# Schematic.net
KiCad netlist of a schematic drawn in Altium Designer
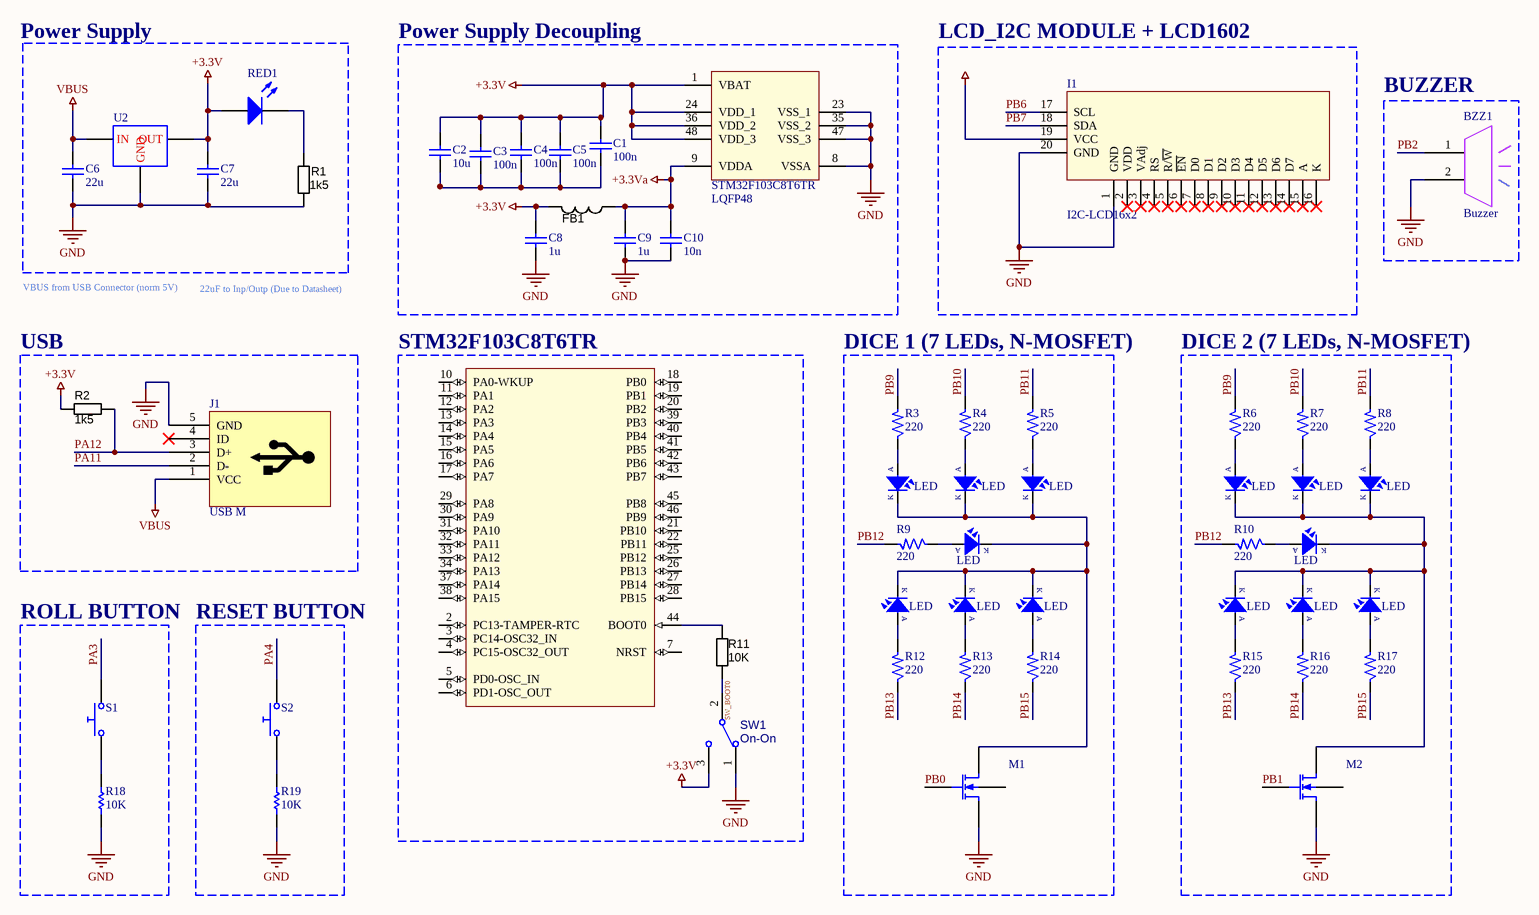
[diagram p0: Schematic.SchDoc]

(export (version "E")
  (design (tool "Eeschema 10.0.6"))
  (components
    (comp (ref "BZZ1")
      (value "Buzzer")
      (footprint "buzzer 5V")
      (libsource (lib "my Library") (part "Buzzer"))
    )
    (comp (ref "C1")
      (value "100n")
      (footprint "C 0402")
      (description "Capacitor")
      (libsource (lib "Simulation Generic Components") (part "Capacitor"))
    )
    (comp (ref "C2")
      (value "10u")
      (footprint "C 0402")
      (description "Capacitor")
      (libsource (lib "Simulation Generic Components") (part "Capacitor"))
    )
    (comp (ref "C3")
      (value "100n")
      (footprint "C 0402")
      (description "Capacitor")
      (libsource (lib "Simulation Generic Components") (part "Capacitor"))
    )
    (comp (ref "C4")
      (value "100n")
      (footprint "C 0402")
      (description "Capacitor")
      (libsource (lib "Simulation Generic Components") (part "Capacitor"))
    )
    (comp (ref "C5")
      (value "100n")
      (footprint "C 0402")
      (description "Capacitor")
      (libsource (lib "Simulation Generic Components") (part "Capacitor"))
    )
    (comp (ref "C6")
      (value "22u")
      (footprint "C 0805")
      (description "Capacitor")
      (libsource (lib "Simulation Generic Components") (part "Capacitor"))
    )
    (comp (ref "C7")
      (value "22u")
      (footprint "C 0805")
      (description "Capacitor")
      (libsource (lib "Simulation Generic Components") (part "Capacitor"))
    )
    (comp (ref "C8")
      (value "1u")
      (footprint "C 0402")
      (description "Capacitor")
      (libsource (lib "Simulation Generic Components") (part "Capacitor"))
    )
    (comp (ref "C9")
      (value "1u")
      (footprint "C 0402")
      (description "Capacitor")
      (libsource (lib "Simulation Generic Components") (part "Capacitor"))
    )
    (comp (ref "C10")
      (value "10n")
      (footprint "C 0402")
      (description "Capacitor")
      (libsource (lib "Simulation Generic Components") (part "Capacitor"))
    )
    (comp (ref "FB1")
      (value "2K2 @ 100 MHz")
      (footprint "FBC1608X95N")
      (description "Ferrite bead 120 Ohm at 100 MHz 200mA 0603 SMD")
      (libsource (lib "my Library") (part "FERRITE_2K2-100MHz_0603"))
    )
    (comp (ref "I1")
      (value "I2C-LCD16x2")
      (footprint "I2C-LCD16X2")
      (description "LCD dipslay 16 char, 2 line")
      (libsource (lib "my Library") (part "I2C-LCD16x2"))
    )
    (comp (ref "J1")
      (value "USB M")
      (footprint "USB-Micr-B-FCI-SMD")
      (libsource (lib "my Library") (part "USB M"))
    )
    (comp (ref "LED1")
      (value "LED")
      (footprint "LED-3")
      (description "LED Single colour Green and Red")
      (libsource (lib "my Library") (part "LED"))
    )
    (comp (ref "LED2")
      (value "LED")
      (footprint "LED-3")
      (description "LED Single colour Green and Red")
      (libsource (lib "my Library") (part "LED"))
    )
    (comp (ref "LED3")
      (value "LED")
      (footprint "LED-3")
      (description "LED Single colour Green and Red")
      (libsource (lib "my Library") (part "LED"))
    )
    (comp (ref "LED4")
      (value "LED")
      (footprint "LED-3")
      (description "LED Single colour Green and Red")
      (libsource (lib "my Library") (part "LED"))
    )
    (comp (ref "LED5")
      (value "LED")
      (footprint "LED-3")
      (description "LED Single colour Green and Red")
      (libsource (lib "my Library") (part "LED"))
    )
    (comp (ref "LED6")
      (value "LED")
      (footprint "LED-3")
      (description "LED Single colour Green and Red")
      (libsource (lib "my Library") (part "LED"))
    )
    (comp (ref "LED7")
      (value "LED")
      (footprint "LED-3")
      (description "LED Single colour Green and Red")
      (libsource (lib "my Library") (part "LED"))
    )
    (comp (ref "LED8")
      (value "LED")
      (footprint "LED-3")
      (description "LED Single colour Green and Red")
      (libsource (lib "my Library") (part "LED"))
    )
    (comp (ref "LED9")
      (value "LED")
      (footprint "LED-3")
      (description "LED Single colour Green and Red")
      (libsource (lib "my Library") (part "LED"))
    )
    (comp (ref "LED10")
      (value "LED")
      (footprint "LED-3")
      (description "LED Single colour Green and Red")
      (libsource (lib "my Library") (part "LED"))
    )
    (comp (ref "LED11")
      (value "LED")
      (footprint "LED-3")
      (description "LED Single colour Green and Red")
      (libsource (lib "my Library") (part "LED"))
    )
    (comp (ref "LED12")
      (value "LED")
      (footprint "LED-3")
      (description "LED Single colour Green and Red")
      (libsource (lib "my Library") (part "LED"))
    )
    (comp (ref "LED13")
      (value "LED")
      (footprint "LED-3")
      (description "LED Single colour Green and Red")
      (libsource (lib "my Library") (part "LED"))
    )
    (comp (ref "LED14")
      (value "LED")
      (footprint "LED-3")
      (description "LED Single colour Green and Red")
      (libsource (lib "my Library") (part "LED"))
    )
    (comp (ref "M1")
      (value "N-channel MOS1 MOSFET Shichman and Hodges Model")
      (libsource (lib "Simulation Generic Components") (part "MOSFET N-ch Lev1"))
    )
    (comp (ref "M2")
      (value "N-channel MOS1 MOSFET Shichman and Hodges Model")
      (libsource (lib "Simulation Generic Components") (part "MOSFET N-ch Lev1"))
    )
    (comp (ref "R1")
      (value "1k5")
      (footprint "RESC1005X40N")
      (description "Resistor SMD chip 1k Ohm 0.063W 5% 0402")
      (fields (field (name "TOLERANCE") "±5%") (field (name "Comment") "Thick Film"))
      (libsource (lib "my Library") (part "RES_0402"))
    )
    (comp (ref "R2")
      (value "1k5")
      (footprint "RESC1005X40N")
      (description "Resistor SMD chip 1k Ohm 0.063W 5% 0402")
      (fields (field (name "TOLERANCE") "±5%") (field (name "Comment") "Thick Film"))
      (libsource (lib "my Library") (part "RES_0402"))
    )
    (comp (ref "R3")
      (value "220")
      (footprint "R1/4W")
      (description "Res")
      (libsource (lib "my Library") (part "Res"))
    )
    (comp (ref "R4")
      (value "220")
      (footprint "R1/4W")
      (description "Res")
      (libsource (lib "my Library") (part "Res"))
    )
    (comp (ref "R5")
      (value "220")
      (footprint "R1/4W")
      (description "Res")
      (libsource (lib "my Library") (part "Res"))
    )
    (comp (ref "R6")
      (value "220")
      (footprint "R1/4W")
      (description "Res")
      (libsource (lib "my Library") (part "Res"))
    )
    (comp (ref "R7")
      (value "220")
      (footprint "R1/4W")
      (description "Res")
      (libsource (lib "my Library") (part "Res"))
    )
    (comp (ref "R8")
      (value "220")
      (footprint "R1/4W")
      (description "Res")
      (libsource (lib "my Library") (part "Res"))
    )
    (comp (ref "R9")
      (value "220")
      (footprint "R1/4W")
      (description "Res")
      (libsource (lib "my Library") (part "Res"))
    )
    (comp (ref "R10")
      (value "220")
      (footprint "R1/4W")
      (description "Res")
      (libsource (lib "my Library") (part "Res"))
    )
    (comp (ref "R11")
      (value "10K")
      (footprint "RESC1005X40N")
      (description "Resistor SMD chip 1k Ohm 0.063W 5% 0402")
      (fields (field (name "TOLERANCE") "±5%") (field (name "Comment") "Thick Film"))
      (libsource (lib "") (part "RES_0402_1"))
    )
    (comp (ref "R12")
      (value "220")
      (footprint "R1/4W")
      (description "Res")
      (libsource (lib "my Library") (part "Res"))
    )
    (comp (ref "R13")
      (value "220")
      (footprint "R1/4W")
      (description "Res")
      (libsource (lib "my Library") (part "Res"))
    )
    (comp (ref "R14")
      (value "220")
      (footprint "R1/4W")
      (description "Res")
      (libsource (lib "my Library") (part "Res"))
    )
    (comp (ref "R15")
      (value "220")
      (footprint "R1/4W")
      (description "Res")
      (libsource (lib "my Library") (part "Res"))
    )
    (comp (ref "R16")
      (value "220")
      (footprint "R1/4W")
      (description "Res")
      (libsource (lib "my Library") (part "Res"))
    )
    (comp (ref "R17")
      (value "220")
      (footprint "R1/4W")
      (description "Res")
      (libsource (lib "my Library") (part "Res"))
    )
    (comp (ref "R18")
      (value "10K")
      (description "Resistor")
      (libsource (lib "Simulation Generic Components") (part "Resistor"))
    )
    (comp (ref "R19")
      (value "10K")
      (description "Resistor")
      (libsource (lib "Simulation Generic Components") (part "Resistor"))
    )
    (comp (ref "RED1")
      (value "Light-Emitting Diode")
      (footprint "LED-RED-0805")
      (libsource (lib "Simulation Generic Components") (part "LED"))
    )
    (comp (ref "S1")
      (value "Push Button Normally Opened")
      (libsource (lib "Simulation Generic Components") (part "Push Button NO"))
    )
    (comp (ref "S2")
      (value "Push Button Normally Opened")
      (libsource (lib "Simulation Generic Components") (part "Push Button NO"))
    )
    (comp (ref "SW1")
      (value "ON-ON")
      (footprint "SW4_SMD")
      (description "Switch THD vertical toggle SPDT")
      (fields (field (name "SWITCH FUNCTION") "On-On"))
      (libsource (lib "my Library") (part "SW_THD_SPDT_On-On"))
    )
    (comp (ref "U1")
      (value "STM32F103C8T6TR")
      (footprint "STM-LQFP48_M")
      (fields (field (name "PACKAGE") "LQFP48"))
      (libsource (lib "mcu_stm32f1") (part "STM32F103C8T6TR"))
    )
    (comp (ref "U2")
      (value "Positive Fixed Voltage regulator")
      (footprint "AMS1117_3v3")
      (libsource (lib "Simulation Generic Components") (part "Linear Voltage Regulator (Fixed)"))
    )
  )
  (nets
    (net (code "1") (name "+3.3V") (class "Default")
      (node (ref "C1") (pin "1") (pinfunction "1_1") (pintype "passive"))
      (node (ref "C2") (pin "1") (pinfunction "1_1") (pintype "passive"))
      (node (ref "C3") (pin "1") (pinfunction "1_1") (pintype "passive"))
      (node (ref "C4") (pin "1") (pinfunction "1_1") (pintype "passive"))
      (node (ref "C5") (pin "1") (pinfunction "1_1") (pintype "passive"))
      (node (ref "C7") (pin "1") (pinfunction "1_1") (pintype "passive"))
      (node (ref "C8") (pin "1") (pinfunction "1_1") (pintype "passive"))
      (node (ref "FB1") (pin "2") (pinfunction "2_2") (pintype "passive"))
      (node (ref "R2") (pin "1") (pinfunction "1_1") (pintype "passive"))
      (node (ref "RED1") (pin "1") (pinfunction "A_1") (pintype "passive"))
      (node (ref "SW1") (pin "3") (pinfunction "3_3") (pintype "passive"))
      (node (ref "U1") (pin "1") (pinfunction "VBAT_1") (pintype "power_in"))
      (node (ref "U1") (pin "24") (pinfunction "VDD_1_24") (pintype "power_in"))
      (node (ref "U1") (pin "36") (pinfunction "VDD_2_36") (pintype "power_in"))
      (node (ref "U1") (pin "48") (pinfunction "VDD_3_48") (pintype "power_in"))
      (node (ref "U2") (pin "3") (pinfunction "OUT_3") (pintype "passive"))
    )
    (net (code "2") (name "+3.3Va") (class "Default")
      (node (ref "C10") (pin "1") (pinfunction "1_1") (pintype "passive"))
      (node (ref "C9") (pin "1") (pinfunction "1_1") (pintype "passive"))
      (node (ref "FB1") (pin "1") (pinfunction "1_1") (pintype "passive"))
      (node (ref "U1") (pin "9") (pinfunction "VDDA_9") (pintype "power_in"))
    )
    (net (code "3") (name "/PA3") (class "Default")
      (node (ref "S1") (pin "2") (pinfunction "2_2") (pintype "passive"))
    )
    (net (code "4") (name "/PA4") (class "Default")
      (node (ref "S2") (pin "2") (pinfunction "2_2") (pintype "passive"))
    )
    (net (code "5") (name "/PA11") (class "Default")
      (node (ref "J1") (pin "2") (pinfunction "D-_2") (pintype "passive"))
    )
    (net (code "6") (name "/PA12") (class "Default")
      (node (ref "J1") (pin "3") (pinfunction "D+_3") (pintype "passive"))
      (node (ref "R2") (pin "2") (pinfunction "2_2") (pintype "passive"))
    )
    (net (code "7") (name "/PB0") (class "Default")
      (node (ref "M1") (pin "2") (pinfunction "G_2") (pintype "passive"))
    )
    (net (code "8") (name "/PB1") (class "Default")
      (node (ref "M2") (pin "2") (pinfunction "G_2") (pintype "passive"))
    )
    (net (code "9") (name "/PB2") (class "Default")
      (node (ref "BZZ1") (pin "1") (pinfunction "1_1") (pintype "passive"))
    )
    (net (code "10") (name "/PB6") (class "Default")
      (node (ref "I1") (pin "17") (pinfunction "SCL_17") (pintype "passive"))
    )
    (net (code "11") (name "/PB7") (class "Default")
      (node (ref "I1") (pin "18") (pinfunction "SDA_18") (pintype "passive"))
    )
    (net (code "12") (name "/PB9") (class "Default")
      (node (ref "R3") (pin "2") (pinfunction "2_2") (pintype "passive"))
      (node (ref "R6") (pin "2") (pinfunction "2_2") (pintype "passive"))
    )
    (net (code "13") (name "/PB10") (class "Default")
      (node (ref "R4") (pin "2") (pinfunction "2_2") (pintype "passive"))
      (node (ref "R7") (pin "2") (pinfunction "2_2") (pintype "passive"))
    )
    (net (code "14") (name "/PB11") (class "Default")
      (node (ref "R5") (pin "2") (pinfunction "2_2") (pintype "passive"))
      (node (ref "R8") (pin "2") (pinfunction "2_2") (pintype "passive"))
    )
    (net (code "15") (name "/PB12") (class "Default")
      (node (ref "R10") (pin "2") (pinfunction "2_2") (pintype "passive"))
      (node (ref "R9") (pin "2") (pinfunction "2_2") (pintype "passive"))
    )
    (net (code "16") (name "/PB13") (class "Default")
      (node (ref "R12") (pin "1") (pinfunction "1_1") (pintype "passive"))
      (node (ref "R15") (pin "1") (pinfunction "1_1") (pintype "passive"))
    )
    (net (code "17") (name "/PB14") (class "Default")
      (node (ref "R13") (pin "1") (pinfunction "1_1") (pintype "passive"))
      (node (ref "R16") (pin "1") (pinfunction "1_1") (pintype "passive"))
    )
    (net (code "18") (name "/PB15") (class "Default")
      (node (ref "R14") (pin "1") (pinfunction "1_1") (pintype "passive"))
      (node (ref "R17") (pin "1") (pinfunction "1_1") (pintype "passive"))
    )
    (net (code "19") (name "/SW_BOOT0") (class "Default")
      (node (ref "R11") (pin "2") (pinfunction "2_2") (pintype "passive"))
      (node (ref "SW1") (pin "2") (pinfunction "2_2") (pintype "passive"))
    )
    (net (code "20") (name "<NO NET>") (class "Default")
      (node (ref "I1") (pin "19") (pinfunction "VCC_19") (pintype "passive"))
    )
    (net (code "21") (name "GND") (class "Default")
      (node (ref "BZZ1") (pin "2") (pinfunction "2_2") (pintype "passive"))
      (node (ref "C10") (pin "2") (pinfunction "2_2") (pintype "passive"))
      (node (ref "C6") (pin "2") (pinfunction "2_2") (pintype "passive"))
      (node (ref "C7") (pin "2") (pinfunction "2_2") (pintype "passive"))
      (node (ref "C8") (pin "2") (pinfunction "2_2") (pintype "passive"))
      (node (ref "C9") (pin "2") (pinfunction "2_2") (pintype "passive"))
      (node (ref "I1") (pin "1") (pinfunction "GND_1") (pintype "passive"))
      (node (ref "I1") (pin "20") (pinfunction "GND_20") (pintype "passive"))
      (node (ref "J1") (pin "5") (pinfunction "GND_5") (pintype "passive"))
      (node (ref "M1") (pin "3") (pinfunction "S_3") (pintype "passive"))
      (node (ref "M2") (pin "3") (pinfunction "S_3") (pintype "passive"))
      (node (ref "R1") (pin "1") (pinfunction "1_1") (pintype "passive"))
      (node (ref "R18") (pin "1") (pinfunction "1_1") (pintype "passive"))
      (node (ref "R19") (pin "1") (pinfunction "1_1") (pintype "passive"))
      (node (ref "SW1") (pin "1") (pinfunction "1_1") (pintype "passive"))
      (node (ref "U1") (pin "23") (pinfunction "VSS_1_23") (pintype "power_in"))
      (node (ref "U1") (pin "35") (pinfunction "VSS_2_35") (pintype "power_in"))
      (node (ref "U1") (pin "47") (pinfunction "VSS_3_47") (pintype "power_in"))
      (node (ref "U1") (pin "8") (pinfunction "VSSA_8") (pintype "power_in"))
      (node (ref "U2") (pin "2") (pinfunction "GND_2") (pintype "passive"))
    )
    (net (code "22") (name "Net-(C1-Pad2)") (class "Default")
      (node (ref "C1") (pin "2") (pinfunction "2_2") (pintype "passive"))
      (node (ref "C2") (pin "2") (pinfunction "2_2") (pintype "passive"))
      (node (ref "C3") (pin "2") (pinfunction "2_2") (pintype "passive"))
      (node (ref "C4") (pin "2") (pinfunction "2_2") (pintype "passive"))
      (node (ref "C5") (pin "2") (pinfunction "2_2") (pintype "passive"))
    )
    (net (code "23") (name "Net-(LED1-A)") (class "Default")
      (node (ref "LED1") (pin "1") (pinfunction "A_1") (pintype "passive"))
      (node (ref "R3") (pin "1") (pinfunction "1_1") (pintype "passive"))
    )
    (net (code "24") (name "Net-(LED1-K)") (class "Default")
      (node (ref "LED1") (pin "2") (pinfunction "K_2") (pintype "passive"))
      (node (ref "LED10") (pin "2") (pinfunction "K_2") (pintype "passive"))
      (node (ref "LED11") (pin "2") (pinfunction "K_2") (pintype "passive"))
      (node (ref "LED2") (pin "2") (pinfunction "K_2") (pintype "passive"))
      (node (ref "LED3") (pin "2") (pinfunction "K_2") (pintype "passive"))
      (node (ref "LED7") (pin "2") (pinfunction "K_2") (pintype "passive"))
      (node (ref "LED9") (pin "2") (pinfunction "K_2") (pintype "passive"))
      (node (ref "M1") (pin "1") (pinfunction "D_1") (pintype "passive"))
    )
    (net (code "25") (name "Net-(LED2-A)") (class "Default")
      (node (ref "LED2") (pin "1") (pinfunction "A_1") (pintype "passive"))
      (node (ref "R4") (pin "1") (pinfunction "1_1") (pintype "passive"))
    )
    (net (code "26") (name "Net-(LED3-A)") (class "Default")
      (node (ref "LED3") (pin "1") (pinfunction "A_1") (pintype "passive"))
      (node (ref "R5") (pin "1") (pinfunction "1_1") (pintype "passive"))
    )
    (net (code "27") (name "Net-(LED4-A)") (class "Default")
      (node (ref "LED4") (pin "1") (pinfunction "A_1") (pintype "passive"))
      (node (ref "R6") (pin "1") (pinfunction "1_1") (pintype "passive"))
    )
    (net (code "28") (name "Net-(LED5-A)") (class "Default")
      (node (ref "LED5") (pin "1") (pinfunction "A_1") (pintype "passive"))
      (node (ref "R7") (pin "1") (pinfunction "1_1") (pintype "passive"))
    )
    (net (code "29") (name "Net-(LED6-A)") (class "Default")
      (node (ref "LED6") (pin "1") (pinfunction "A_1") (pintype "passive"))
      (node (ref "R8") (pin "1") (pinfunction "1_1") (pintype "passive"))
    )
    (net (code "30") (name "Net-(LED7-A)") (class "Default")
      (node (ref "LED7") (pin "1") (pinfunction "A_1") (pintype "passive"))
      (node (ref "R9") (pin "1") (pinfunction "1_1") (pintype "passive"))
    )
    (net (code "31") (name "Net-(LED8-A)") (class "Default")
      (node (ref "LED8") (pin "1") (pinfunction "A_1") (pintype "passive"))
      (node (ref "R10") (pin "1") (pinfunction "1_1") (pintype "passive"))
    )
    (net (code "32") (name "Net-(LED9-A)") (class "Default")
      (node (ref "LED9") (pin "1") (pinfunction "A_1") (pintype "passive"))
      (node (ref "R12") (pin "2") (pinfunction "2_2") (pintype "passive"))
    )
    (net (code "33") (name "Net-(LED10-A)") (class "Default")
      (node (ref "LED10") (pin "1") (pinfunction "A_1") (pintype "passive"))
      (node (ref "R13") (pin "2") (pinfunction "2_2") (pintype "passive"))
    )
    (net (code "34") (name "Net-(LED11-A)") (class "Default")
      (node (ref "LED11") (pin "1") (pinfunction "A_1") (pintype "passive"))
      (node (ref "R14") (pin "2") (pinfunction "2_2") (pintype "passive"))
    )
    (net (code "35") (name "Net-(LED12-A)") (class "Default")
      (node (ref "LED12") (pin "1") (pinfunction "A_1") (pintype "passive"))
      (node (ref "R15") (pin "2") (pinfunction "2_2") (pintype "passive"))
    )
    (net (code "36") (name "Net-(LED12-K)") (class "Default")
      (node (ref "LED12") (pin "2") (pinfunction "K_2") (pintype "passive"))
      (node (ref "LED13") (pin "2") (pinfunction "K_2") (pintype "passive"))
      (node (ref "LED14") (pin "2") (pinfunction "K_2") (pintype "passive"))
      (node (ref "LED4") (pin "2") (pinfunction "K_2") (pintype "passive"))
      (node (ref "LED5") (pin "2") (pinfunction "K_2") (pintype "passive"))
      (node (ref "LED6") (pin "2") (pinfunction "K_2") (pintype "passive"))
      (node (ref "LED8") (pin "2") (pinfunction "K_2") (pintype "passive"))
      (node (ref "M2") (pin "1") (pinfunction "D_1") (pintype "passive"))
    )
    (net (code "37") (name "Net-(LED13-A)") (class "Default")
      (node (ref "LED13") (pin "1") (pinfunction "A_1") (pintype "passive"))
      (node (ref "R16") (pin "2") (pinfunction "2_2") (pintype "passive"))
    )
    (net (code "38") (name "Net-(LED14-A)") (class "Default")
      (node (ref "LED14") (pin "1") (pinfunction "A_1") (pintype "passive"))
      (node (ref "R17") (pin "2") (pinfunction "2_2") (pintype "passive"))
    )
    (net (code "39") (name "Net-(R18-Pad2)") (class "Default")
      (node (ref "R18") (pin "2") (pinfunction "2_2") (pintype "passive"))
      (node (ref "S1") (pin "1") (pinfunction "1_1") (pintype "passive"))
    )
    (net (code "40") (name "Net-(R19-Pad2)") (class "Default")
      (node (ref "R19") (pin "2") (pinfunction "2_2") (pintype "passive"))
      (node (ref "S2") (pin "1") (pinfunction "1_1") (pintype "passive"))
    )
    (net (code "41") (name "Net-(RED1-K)") (class "Default")
      (node (ref "R1") (pin "2") (pinfunction "2_2") (pintype "passive"))
      (node (ref "RED1") (pin "2") (pinfunction "K_2") (pintype "passive"))
    )
    (net (code "42") (name "Net-(U1A-BOOT0)") (class "Default")
      (node (ref "R11") (pin "1") (pinfunction "1_1") (pintype "passive"))
      (node (ref "U1") (pin "44") (pinfunction "BOOT0_44") (pintype "input"))
    )
    (net (code "43") (name "VBUS") (class "Default")
      (node (ref "C6") (pin "1") (pinfunction "1_1") (pintype "passive"))
      (node (ref "J1") (pin "1") (pinfunction "VCC_1") (pintype "passive"))
      (node (ref "U2") (pin "1") (pinfunction "IN_1") (pintype "passive"))
    )
    (net (code "44") (name "unconnected-(I1-A-Pad15)") (class "Default")
      (node (ref "I1") (pin "15") (pinfunction "A_15") (pintype "passive+no_connect"))
    )
    (net (code "45") (name "unconnected-(I1-D0-Pad7)") (class "Default")
      (node (ref "I1") (pin "7") (pinfunction "D0_7") (pintype "passive+no_connect"))
    )
    (net (code "46") (name "unconnected-(I1-D1-Pad8)") (class "Default")
      (node (ref "I1") (pin "8") (pinfunction "D1_8") (pintype "passive+no_connect"))
    )
    (net (code "47") (name "unconnected-(I1-D2-Pad9)") (class "Default")
      (node (ref "I1") (pin "9") (pinfunction "D2_9") (pintype "passive+no_connect"))
    )
    (net (code "48") (name "unconnected-(I1-D3-Pad10)") (class "Default")
      (node (ref "I1") (pin "10") (pinfunction "D3_10") (pintype "passive+no_connect"))
    )
    (net (code "49") (name "unconnected-(I1-D4-Pad11)") (class "Default")
      (node (ref "I1") (pin "11") (pinfunction "D4_11") (pintype "passive+no_connect"))
    )
    (net (code "50") (name "unconnected-(I1-D5-Pad12)") (class "Default")
      (node (ref "I1") (pin "12") (pinfunction "D5_12") (pintype "passive+no_connect"))
    )
    (net (code "51") (name "unconnected-(I1-D6-Pad13)") (class "Default")
      (node (ref "I1") (pin "13") (pinfunction "D6_13") (pintype "passive+no_connect"))
    )
    (net (code "52") (name "unconnected-(I1-D7-Pad14)") (class "Default")
      (node (ref "I1") (pin "14") (pinfunction "D7_14") (pintype "passive+no_connect"))
    )
    (net (code "53") (name "unconnected-(I1-K-Pad16)") (class "Default")
      (node (ref "I1") (pin "16") (pinfunction "K_16") (pintype "passive+no_connect"))
    )
    (net (code "54") (name "unconnected-(I1-RS-Pad4)") (class "Default")
      (node (ref "I1") (pin "4") (pinfunction "RS_4") (pintype "passive+no_connect"))
    )
    (net (code "55") (name "unconnected-(I1-R{slash}~{W}-Pad5)") (class "Default")
      (node (ref "I1") (pin "5") (pinfunction "R/~{W}_5") (pintype "passive+no_connect"))
    )
    (net (code "56") (name "unconnected-(I1-VAdj-Pad3)") (class "Default")
      (node (ref "I1") (pin "3") (pinfunction "VAdj_3") (pintype "passive+no_connect"))
    )
    (net (code "57") (name "unconnected-(I1-VDD-Pad2)") (class "Default")
      (node (ref "I1") (pin "2") (pinfunction "VDD_2") (pintype "passive+no_connect"))
    )
    (net (code "58") (name "unconnected-(I1-~{EN}-Pad6)") (class "Default")
      (node (ref "I1") (pin "6") (pinfunction "~{EN}_6") (pintype "passive+no_connect"))
    )
    (net (code "59") (name "unconnected-(J1-ID-Pad4)") (class "Default")
      (node (ref "J1") (pin "4") (pinfunction "ID_4") (pintype "passive+no_connect"))
    )
    (net (code "60") (name "unconnected-(M1-B-Pad4)") (class "Default")
      (node (ref "M1") (pin "4") (pinfunction "B_4") (pintype "passive"))
    )
    (net (code "61") (name "unconnected-(M2-B-Pad4)") (class "Default")
      (node (ref "M2") (pin "4") (pinfunction "B_4") (pintype "passive"))
    )
    (net (code "62") (name "unconnected-(U1A-NRST-Pad7)") (class "Default")
      (node (ref "U1") (pin "7") (pinfunction "NRST_7") (pintype "bidirectional"))
    )
    (net (code "63") (name "unconnected-(U1A-PA0-WKUP-Pad10)") (class "Default")
      (node (ref "U1") (pin "10") (pinfunction "PA0-WKUP_10") (pintype "bidirectional"))
    )
    (net (code "64") (name "unconnected-(U1A-PA1-Pad11)") (class "Default")
      (node (ref "U1") (pin "11") (pinfunction "PA1_11") (pintype "bidirectional"))
    )
    (net (code "65") (name "unconnected-(U1A-PA2-Pad12)") (class "Default")
      (node (ref "U1") (pin "12") (pinfunction "PA2_12") (pintype "bidirectional"))
    )
    (net (code "66") (name "unconnected-(U1A-PA3-Pad13)") (class "Default")
      (node (ref "U1") (pin "13") (pinfunction "PA3_13") (pintype "bidirectional"))
    )
    (net (code "67") (name "unconnected-(U1A-PA4-Pad14)") (class "Default")
      (node (ref "U1") (pin "14") (pinfunction "PA4_14") (pintype "bidirectional"))
    )
    (net (code "68") (name "unconnected-(U1A-PA5-Pad15)") (class "Default")
      (node (ref "U1") (pin "15") (pinfunction "PA5_15") (pintype "bidirectional"))
    )
    (net (code "69") (name "unconnected-(U1A-PA6-Pad16)") (class "Default")
      (node (ref "U1") (pin "16") (pinfunction "PA6_16") (pintype "bidirectional"))
    )
    (net (code "70") (name "unconnected-(U1A-PA7-Pad17)") (class "Default")
      (node (ref "U1") (pin "17") (pinfunction "PA7_17") (pintype "bidirectional"))
    )
    (net (code "71") (name "unconnected-(U1A-PA8-Pad29)") (class "Default")
      (node (ref "U1") (pin "29") (pinfunction "PA8_29") (pintype "bidirectional"))
    )
    (net (code "72") (name "unconnected-(U1A-PA9-Pad30)") (class "Default")
      (node (ref "U1") (pin "30") (pinfunction "PA9_30") (pintype "bidirectional"))
    )
    (net (code "73") (name "unconnected-(U1A-PA10-Pad31)") (class "Default")
      (node (ref "U1") (pin "31") (pinfunction "PA10_31") (pintype "bidirectional"))
    )
    (net (code "74") (name "unconnected-(U1A-PA11-Pad32)") (class "Default")
      (node (ref "U1") (pin "32") (pinfunction "PA11_32") (pintype "bidirectional"))
    )
    (net (code "75") (name "unconnected-(U1A-PA12-Pad33)") (class "Default")
      (node (ref "U1") (pin "33") (pinfunction "PA12_33") (pintype "bidirectional"))
    )
    (net (code "76") (name "unconnected-(U1A-PA13-Pad34)") (class "Default")
      (node (ref "U1") (pin "34") (pinfunction "PA13_34") (pintype "bidirectional"))
    )
    (net (code "77") (name "unconnected-(U1A-PA14-Pad37)") (class "Default")
      (node (ref "U1") (pin "37") (pinfunction "PA14_37") (pintype "bidirectional"))
    )
    (net (code "78") (name "unconnected-(U1A-PA15-Pad38)") (class "Default")
      (node (ref "U1") (pin "38") (pinfunction "PA15_38") (pintype "bidirectional"))
    )
    (net (code "79") (name "unconnected-(U1A-PB0-Pad18)") (class "Default")
      (node (ref "U1") (pin "18") (pinfunction "PB0_18") (pintype "bidirectional"))
    )
    (net (code "80") (name "unconnected-(U1A-PB1-Pad19)") (class "Default")
      (node (ref "U1") (pin "19") (pinfunction "PB1_19") (pintype "bidirectional"))
    )
    (net (code "81") (name "unconnected-(U1A-PB2-Pad20)") (class "Default")
      (node (ref "U1") (pin "20") (pinfunction "PB2_20") (pintype "bidirectional"))
    )
    (net (code "82") (name "unconnected-(U1A-PB3-Pad39)") (class "Default")
      (node (ref "U1") (pin "39") (pinfunction "PB3_39") (pintype "bidirectional"))
    )
    (net (code "83") (name "unconnected-(U1A-PB4-Pad40)") (class "Default")
      (node (ref "U1") (pin "40") (pinfunction "PB4_40") (pintype "bidirectional"))
    )
    (net (code "84") (name "unconnected-(U1A-PB5-Pad41)") (class "Default")
      (node (ref "U1") (pin "41") (pinfunction "PB5_41") (pintype "bidirectional"))
    )
    (net (code "85") (name "unconnected-(U1A-PB6-Pad42)") (class "Default")
      (node (ref "U1") (pin "42") (pinfunction "PB6_42") (pintype "bidirectional"))
    )
    (net (code "86") (name "unconnected-(U1A-PB7-Pad43)") (class "Default")
      (node (ref "U1") (pin "43") (pinfunction "PB7_43") (pintype "bidirectional"))
    )
    (net (code "87") (name "unconnected-(U1A-PB8-Pad45)") (class "Default")
      (node (ref "U1") (pin "45") (pinfunction "PB8_45") (pintype "bidirectional"))
    )
    (net (code "88") (name "unconnected-(U1A-PB9-Pad46)") (class "Default")
      (node (ref "U1") (pin "46") (pinfunction "PB9_46") (pintype "bidirectional"))
    )
    (net (code "89") (name "unconnected-(U1A-PB10-Pad21)") (class "Default")
      (node (ref "U1") (pin "21") (pinfunction "PB10_21") (pintype "bidirectional"))
    )
    (net (code "90") (name "unconnected-(U1A-PB11-Pad22)") (class "Default")
      (node (ref "U1") (pin "22") (pinfunction "PB11_22") (pintype "bidirectional"))
    )
    (net (code "91") (name "unconnected-(U1A-PB12-Pad25)") (class "Default")
      (node (ref "U1") (pin "25") (pinfunction "PB12_25") (pintype "bidirectional"))
    )
    (net (code "92") (name "unconnected-(U1A-PB13-Pad26)") (class "Default")
      (node (ref "U1") (pin "26") (pinfunction "PB13_26") (pintype "bidirectional"))
    )
    (net (code "93") (name "unconnected-(U1A-PB14-Pad27)") (class "Default")
      (node (ref "U1") (pin "27") (pinfunction "PB14_27") (pintype "bidirectional"))
    )
    (net (code "94") (name "unconnected-(U1A-PB15-Pad28)") (class "Default")
      (node (ref "U1") (pin "28") (pinfunction "PB15_28") (pintype "bidirectional"))
    )
    (net (code "95") (name "unconnected-(U1A-PC13-TAMPER-RTC-Pad2)") (class "Default")
      (node (ref "U1") (pin "2") (pinfunction "PC13-TAMPER-RTC_2") (pintype "bidirectional"))
    )
    (net (code "96") (name "unconnected-(U1A-PC14-OSC32_IN-Pad3)") (class "Default")
      (node (ref "U1") (pin "3") (pinfunction "PC14-OSC32_IN_3") (pintype "bidirectional"))
    )
    (net (code "97") (name "unconnected-(U1A-PC15-OSC32_OUT-Pad4)") (class "Default")
      (node (ref "U1") (pin "4") (pinfunction "PC15-OSC32_OUT_4") (pintype "bidirectional"))
    )
    (net (code "98") (name "unconnected-(U1A-PD0-OSC_IN-Pad5)") (class "Default")
      (node (ref "U1") (pin "5") (pinfunction "PD0-OSC_IN_5") (pintype "bidirectional"))
    )
    (net (code "99") (name "unconnected-(U1A-PD1-OSC_OUT-Pad6)") (class "Default")
      (node (ref "U1") (pin "6") (pinfunction "PD1-OSC_OUT_6") (pintype "bidirectional"))
    )
  )
)
